# SCH_3_Heartrate_Motion_Sensors.net
KiCad netlist of a schematic drawn in Altium Designer
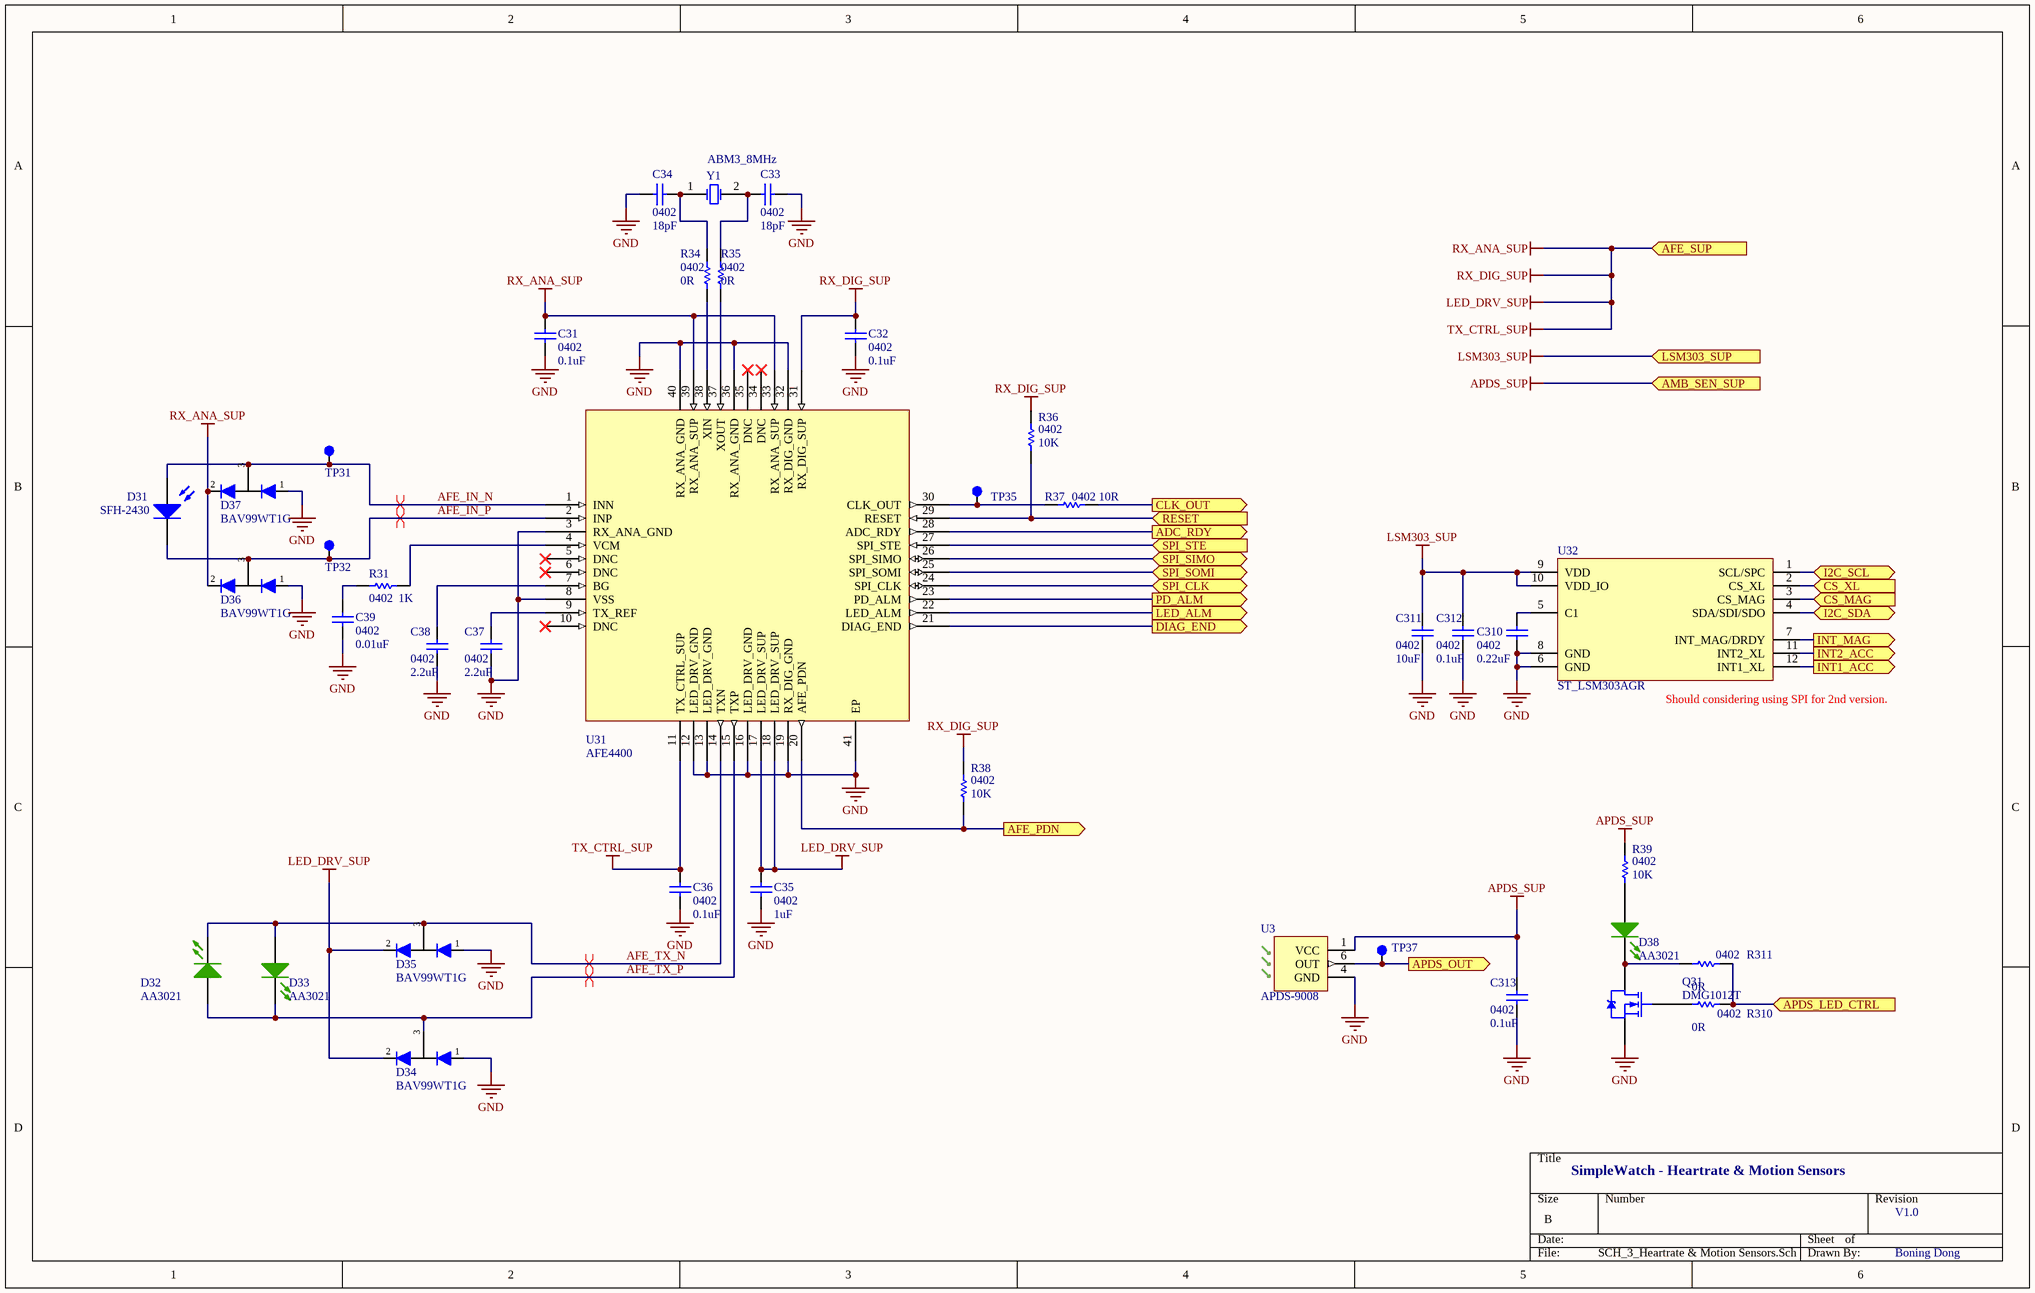
[diagram p0: SCH_3_Heartrate & Motion Sensors.SchDoc]

(export (version "E")
  (design (tool "Eeschema 10.0.6"))
  (components
    (comp (ref "C31")
      (value "0402")
      (footprint "CAPC1005X07N")
      (description "Capacitor")
      (fields (field (name "ALTIUM_VALUE") "0.1uF") (field (name "PUBLISHER") "Altium Limited"))
      (libsource (lib "Miscellaneous Devices") (part "Cap"))
    )
    (comp (ref "C32")
      (value "0402")
      (footprint "CAPC1005X07N")
      (description "Capacitor")
      (fields (field (name "ALTIUM_VALUE") "0.1uF") (field (name "PUBLISHER") "Altium Limited"))
      (libsource (lib "Miscellaneous Devices") (part "Cap"))
    )
    (comp (ref "C33")
      (value "0402")
      (footprint "CAPC1005X07N")
      (description "Capacitor")
      (fields (field (name "ALTIUM_VALUE") "18pF") (field (name "PUBLISHER") "Altium Limited"))
      (libsource (lib "Miscellaneous Devices") (part "Cap"))
    )
    (comp (ref "C34")
      (value "0402")
      (footprint "CAPC1005X07N")
      (description "Capacitor")
      (fields (field (name "ALTIUM_VALUE") "18pF") (field (name "PUBLISHER") "Altium Limited"))
      (libsource (lib "Miscellaneous Devices") (part "Cap"))
    )
    (comp (ref "C35")
      (value "0402")
      (footprint "CAPC1005X07N")
      (description "Capacitor")
      (fields (field (name "ALTIUM_VALUE") "1uF") (field (name "PUBLISHER") "Altium Limited"))
      (libsource (lib "Miscellaneous Devices") (part "Cap"))
    )
    (comp (ref "C36")
      (value "0402")
      (footprint "CAPC1005X07N")
      (description "Capacitor")
      (fields (field (name "ALTIUM_VALUE") "0.1uF") (field (name "PUBLISHER") "Altium Limited"))
      (libsource (lib "Miscellaneous Devices") (part "Cap"))
    )
    (comp (ref "C37")
      (value "0402")
      (footprint "CAPC1005X07N")
      (description "Capacitor")
      (fields (field (name "ALTIUM_VALUE") "2.2uF") (field (name "PUBLISHER") "Altium Limited"))
      (libsource (lib "Miscellaneous Devices") (part "Cap"))
    )
    (comp (ref "C38")
      (value "0402")
      (footprint "CAPC1005X07N")
      (description "Capacitor")
      (fields (field (name "ALTIUM_VALUE") "2.2uF") (field (name "PUBLISHER") "Altium Limited"))
      (libsource (lib "Miscellaneous Devices") (part "Cap"))
    )
    (comp (ref "C39")
      (value "0402")
      (footprint "CAPC1005X07N")
      (description "Capacitor")
      (fields (field (name "ALTIUM_VALUE") "0.01uF") (field (name "PUBLISHER") "Altium Limited"))
      (libsource (lib "Miscellaneous Devices") (part "Cap"))
    )
    (comp (ref "C310")
      (value "0402")
      (footprint "CAPC1005X07N")
      (description "Capacitor")
      (fields (field (name "ALTIUM_VALUE") "0.22uF") (field (name "PUBLISHER") "Altium Limited"))
      (libsource (lib "Miscellaneous Devices") (part "Cap"))
    )
    (comp (ref "C311")
      (value "0402")
      (footprint "CAPC1005X07N")
      (description "Capacitor")
      (fields (field (name "ALTIUM_VALUE") "10uF") (field (name "PUBLISHER") "Altium Limited"))
      (libsource (lib "Miscellaneous Devices") (part "Cap"))
    )
    (comp (ref "C312")
      (value "0402")
      (footprint "CAPC1005X07N")
      (description "Capacitor")
      (fields (field (name "ALTIUM_VALUE") "0.1uF") (field (name "PUBLISHER") "Altium Limited"))
      (libsource (lib "Miscellaneous Devices") (part "Cap"))
    )
    (comp (ref "C313")
      (value "0402")
      (footprint "CAPC1005X07N")
      (description "Capacitor")
      (fields (field (name "ALTIUM_VALUE") "0.1uF") (field (name "PUBLISHER") "Altium Limited"))
      (libsource (lib "Miscellaneous Devices") (part "Cap"))
    )
    (comp (ref "D31")
      (value "SFH-2430")
      (footprint "PHOTODIODE_OSRAM_SFH_2430")
      (description "Photosensitive Diode")
      (fields (field (name "PUBLISHER") "Altium Limited"))
      (libsource (lib "Miscellaneous Devices") (part "Photo Sen"))
    )
    (comp (ref "D32")
      (value "AA3021")
      (footprint "LED_KINGBRIGHT_AA3021")
      (description "General Green LED")
      (libsource (lib "Schematic_Diode") (part "LED_GREEN"))
    )
    (comp (ref "D33")
      (value "AA3021")
      (footprint "LED_KINGBRIGHT_AA3021")
      (description "General Green LED")
      (libsource (lib "Schematic_Diode") (part "LED_GREEN"))
    )
    (comp (ref "D34")
      (value "BAV99WT1G")
      (footprint "SOT65P200X125X90-3N")
      (description "DIODE ARRAY GP 100V 215MA SC70-3")
      (libsource (lib "Schematic_Diode") (part "BAV99WT1"))
    )
    (comp (ref "D35")
      (value "BAV99WT1G")
      (footprint "SOT65P200X125X90-3N")
      (description "DIODE ARRAY GP 100V 215MA SC70-3")
      (libsource (lib "Schematic_Diode") (part "BAV99WT1"))
    )
    (comp (ref "D36")
      (value "BAV99WT1G")
      (footprint "SOT65P200X125X90-3N")
      (description "DIODE ARRAY GP 100V 215MA SC70-3")
      (libsource (lib "Schematic_Diode") (part "BAV99WT1"))
    )
    (comp (ref "D37")
      (value "BAV99WT1G")
      (footprint "SOT65P200X125X90-3N")
      (description "DIODE ARRAY GP 100V 215MA SC70-3")
      (libsource (lib "Schematic_Diode") (part "BAV99WT1"))
    )
    (comp (ref "D38")
      (value "AA3021")
      (footprint "LED_KINGBRIGHT_AA3021")
      (description "General Green LED")
      (libsource (lib "Schematic_Diode") (part "LED_GREEN"))
    )
    (comp (ref "Q31")
      (value "DMG1012T")
      (footprint "SOT65P200X125X95-3N")
      (description "MOSFET N-CH 20V 630MA SOT-523")
      (fields (field (name "MANUFACTURER") "Diodes") (field (name "MANUFACTURER PART NUMBER") "DMG1012T-7"))
      (libsource (lib "Schematic_Transistors") (part "DMG1012T-7"))
    )
    (comp (ref "R31")
      (value "0402")
      (footprint "RESC1005X04N")
      (description "Resistor")
      (fields (field (name "ALTIUM_VALUE") "1K") (field (name "PUBLISHER") "Altium Limited"))
      (libsource (lib "Miscellaneous Devices") (part "Res1"))
    )
    (comp (ref "R34")
      (value "0402")
      (footprint "RESC1005X04N")
      (description "Resistor")
      (fields (field (name "ALTIUM_VALUE") "0R") (field (name "PUBLISHER") "Altium Limited"))
      (libsource (lib "Miscellaneous Devices") (part "Res1"))
    )
    (comp (ref "R35")
      (value "0402")
      (footprint "RESC1005X04N")
      (description "Resistor")
      (fields (field (name "ALTIUM_VALUE") "0R") (field (name "PUBLISHER") "Altium Limited"))
      (libsource (lib "Miscellaneous Devices") (part "Res1"))
    )
    (comp (ref "R36")
      (value "0402")
      (footprint "RESC1005X04N")
      (description "Resistor")
      (fields (field (name "ALTIUM_VALUE") "10K") (field (name "PUBLISHER") "Altium Limited"))
      (libsource (lib "Miscellaneous Devices") (part "Res1"))
    )
    (comp (ref "R37")
      (value "0402")
      (footprint "RESC1005X04N")
      (description "Resistor")
      (fields (field (name "ALTIUM_VALUE") "10R") (field (name "PUBLISHER") "Altium Limited"))
      (libsource (lib "Miscellaneous Devices") (part "Res1"))
    )
    (comp (ref "R38")
      (value "0402")
      (footprint "RESC1005X04N")
      (description "Resistor")
      (fields (field (name "ALTIUM_VALUE") "10K") (field (name "PUBLISHER") "Altium Limited"))
      (libsource (lib "Miscellaneous Devices") (part "Res1"))
    )
    (comp (ref "R39")
      (value "0402")
      (footprint "RESC1005X04N")
      (description "Resistor")
      (fields (field (name "ALTIUM_VALUE") "10K") (field (name "PUBLISHER") "Altium Limited"))
      (libsource (lib "Miscellaneous Devices") (part "Res1"))
    )
    (comp (ref "R310")
      (value "0402")
      (footprint "RESC1005X04N")
      (description "Resistor")
      (fields (field (name "ALTIUM_VALUE") "0R") (field (name "PUBLISHER") "Altium Limited"))
      (libsource (lib "Miscellaneous Devices") (part "Res1"))
    )
    (comp (ref "R311")
      (value "0402")
      (footprint "RESC1005X04N")
      (description "Resistor")
      (fields (field (name "ALTIUM_VALUE") "0R") (field (name "PUBLISHER") "Altium Limited"))
      (libsource (lib "Miscellaneous Devices") (part "Res1"))
    )
    (comp (ref "TP31")
      (value "TP")
      (footprint "TP100")
      (description "Test Point dot type")
      (libsource (lib "Schematic_Test_Points") (part "TP_A"))
    )
    (comp (ref "TP32")
      (value "TP")
      (footprint "TP100")
      (description "Test Point dot type")
      (libsource (lib "Schematic_Test_Points") (part "TP_A"))
    )
    (comp (ref "TP35")
      (value "TP")
      (footprint "TP100")
      (description "Test Point dot type")
      (libsource (lib "Schematic_Test_Points") (part "TP_A"))
    )
    (comp (ref "TP37")
      (value "TP")
      (footprint "TP100")
      (description "Test Point dot type")
      (libsource (lib "Schematic_Test_Points") (part "TP_A"))
    )
    (comp (ref "U3")
      (value "APDS-9008")
      (footprint "APDS-9008")
      (description "Optical Sensor Ambient 565nm Current 6-SMD, No Lead")
      (libsource (lib "Schematic_IC_Sensors") (part "APDS-9008"))
    )
    (comp (ref "U31")
      (value "AFE4400")
      (footprint "QFN50P600X600X100-40N_HS410")
      (description "Integrated Analog Front End (AFE) for Heart-Rate Monitors and Low-Cost Pulse Oximeters")
      (libsource (lib "Schematic_IC_Special") (part "AFE4400"))
    )
    (comp (ref "U32")
      (value "ST_LSM303AGR")
      (footprint "LGA12S50P4X4_200X200X100")
      (description "Accelerometer, Magnetometer, Temperature, 3 Axis Sensor I²C, SPI Output")
      (libsource (lib "Schematic_IC_Sensors") (part "ST_LSM303AGR"))
    )
    (comp (ref "Y1")
      (value "ABM3_8MHz")
      (footprint "ABRACON_ABM3")
      (description "Crystal Oscillator")
      (fields (field (name "PUBLISHER") "Altium Limited"))
      (libsource (lib "Miscellaneous Devices") (part "XTAL"))
    )
  )
  (nets
    (net (code "1") (name "/ADC_RDY") (class "Default")
      (node (ref "U31") (pin "28") (pinfunction "ADC_RDY_28") (pintype "output"))
    )
    (net (code "2") (name "/AFE_IN_N") (class "Default")
      (node (ref "D31") (pin "1") (pinfunction "A_1") (pintype "passive"))
      (node (ref "D37") (pin "3") (pinfunction "ANODE_3") (pintype "passive"))
      (node (ref "TP31") (pin "1") (pintype "passive"))
      (node (ref "U31") (pin "1") (pinfunction "INN_1") (pintype "input"))
    )
    (net (code "3") (name "/AFE_IN_P") (class "Default")
      (node (ref "D31") (pin "2") (pinfunction "K_2") (pintype "passive"))
      (node (ref "D36") (pin "3") (pinfunction "ANODE_3") (pintype "passive"))
      (node (ref "TP32") (pin "1") (pintype "passive"))
      (node (ref "U31") (pin "2") (pinfunction "INP_2") (pintype "input"))
    )
    (net (code "4") (name "/AFE_PDN") (class "Default")
      (node (ref "R38") (pin "1") (pinfunction "1_1") (pintype "passive"))
      (node (ref "U31") (pin "20") (pinfunction "AFE_PDN_20") (pintype "output"))
    )
    (net (code "5") (name "/AFE_TX_N") (class "Default")
      (node (ref "D32") (pin "2") (pinfunction "K_2") (pintype "passive"))
      (node (ref "D33") (pin "1") (pinfunction "A_1") (pintype "passive"))
      (node (ref "D35") (pin "3") (pinfunction "ANODE_3") (pintype "passive"))
      (node (ref "U31") (pin "14") (pinfunction "TXN_14") (pintype "output"))
    )
    (net (code "6") (name "/AFE_TX_P") (class "Default")
      (node (ref "D32") (pin "1") (pinfunction "A_1") (pintype "passive"))
      (node (ref "D33") (pin "2") (pinfunction "K_2") (pintype "passive"))
      (node (ref "D34") (pin "3") (pinfunction "ANODE_3") (pintype "passive"))
      (node (ref "U31") (pin "15") (pinfunction "TXP_15") (pintype "output"))
    )
    (net (code "7") (name "/APDS_LED_CTRL") (class "Default")
      (node (ref "R310") (pin "1") (pinfunction "1_1") (pintype "passive"))
      (node (ref "R311") (pin "1") (pinfunction "1_1") (pintype "passive"))
    )
    (net (code "8") (name "/APDS_OUT") (class "Default")
      (node (ref "TP37") (pin "1") (pintype "passive"))
      (node (ref "U3") (pin "6") (pinfunction "OUT_6") (pintype "output"))
    )
    (net (code "9") (name "/CLK_OUT") (class "Default")
      (node (ref "R37") (pin "1") (pinfunction "1_1") (pintype "passive"))
    )
    (net (code "10") (name "/CS_MAG") (class "Default")
      (node (ref "U32") (pin "3") (pinfunction "CS_MAG_3") (pintype "passive"))
    )
    (net (code "11") (name "/CS_XL") (class "Default")
      (node (ref "U32") (pin "2") (pinfunction "CS_XL_2") (pintype "passive"))
    )
    (net (code "12") (name "/DIAG_END") (class "Default")
      (node (ref "U31") (pin "21") (pinfunction "DIAG_END_21") (pintype "output"))
    )
    (net (code "13") (name "/I2C_SCL") (class "Default")
      (node (ref "U32") (pin "1") (pinfunction "SCL/SPC_1") (pintype "passive"))
    )
    (net (code "14") (name "/I2C_SDA") (class "Default")
      (node (ref "U32") (pin "4") (pinfunction "SDA/SDI/SDO_4") (pintype "passive"))
    )
    (net (code "15") (name "/INT1_ACC") (class "Default")
      (node (ref "U32") (pin "12") (pinfunction "INT1_XL_12") (pintype "passive"))
    )
    (net (code "16") (name "/INT2_ACC") (class "Default")
      (node (ref "U32") (pin "11") (pinfunction "INT2_XL_11") (pintype "passive"))
    )
    (net (code "17") (name "/INT_MAG") (class "Default")
      (node (ref "U32") (pin "7") (pinfunction "INT_MAG/DRDY_7") (pintype "passive"))
    )
    (net (code "18") (name "/LED_ALM") (class "Default")
      (node (ref "U31") (pin "22") (pinfunction "LED_ALM_22") (pintype "output"))
    )
    (net (code "19") (name "/PD_ALM") (class "Default")
      (node (ref "U31") (pin "23") (pinfunction "PD_ALM_23") (pintype "output"))
    )
    (net (code "20") (name "/RESET") (class "Default")
      (node (ref "R36") (pin "1") (pinfunction "1_1") (pintype "passive"))
      (node (ref "U31") (pin "29") (pinfunction "RESET_29") (pintype "input"))
    )
    (net (code "21") (name "/SPI_CLK") (class "Default")
      (node (ref "U31") (pin "24") (pinfunction "SPI_CLK_24") (pintype "bidirectional"))
    )
    (net (code "22") (name "/SPI_SIMO") (class "Default")
      (node (ref "U31") (pin "26") (pinfunction "SPI_SIMO_26") (pintype "bidirectional"))
    )
    (net (code "23") (name "/SPI_SOMI") (class "Default")
      (node (ref "U31") (pin "25") (pinfunction "SPI_SOMI_25") (pintype "bidirectional"))
    )
    (net (code "24") (name "/SPI_STE") (class "Default")
      (node (ref "U31") (pin "27") (pinfunction "SPI_STE_27") (pintype "input"))
    )
    (net (code "25") (name "APDS_SUP") (class "Default")
      (node (ref "C313") (pin "2") (pinfunction "2_2") (pintype "passive"))
      (node (ref "R39") (pin "2") (pinfunction "2_2") (pintype "passive"))
      (node (ref "U3") (pin "1") (pinfunction "VCC_1") (pintype "passive"))
    )
    (net (code "26") (name "GND") (class "Default")
      (node (ref "C31") (pin "1") (pinfunction "1_1") (pintype "passive"))
      (node (ref "C310") (pin "1") (pinfunction "1_1") (pintype "passive"))
      (node (ref "C311") (pin "1") (pinfunction "1_1") (pintype "passive"))
      (node (ref "C312") (pin "1") (pinfunction "1_1") (pintype "passive"))
      (node (ref "C313") (pin "1") (pinfunction "1_1") (pintype "passive"))
      (node (ref "C32") (pin "1") (pinfunction "1_1") (pintype "passive"))
      (node (ref "C33") (pin "1") (pinfunction "1_1") (pintype "passive"))
      (node (ref "C34") (pin "2") (pinfunction "2_2") (pintype "passive"))
      (node (ref "C35") (pin "1") (pinfunction "1_1") (pintype "passive"))
      (node (ref "C36") (pin "1") (pinfunction "1_1") (pintype "passive"))
      (node (ref "C37") (pin "1") (pinfunction "1_1") (pintype "passive"))
      (node (ref "C38") (pin "1") (pinfunction "1_1") (pintype "passive"))
      (node (ref "C39") (pin "1") (pinfunction "1_1") (pintype "passive"))
      (node (ref "D34") (pin "1") (pinfunction "ANODE_1") (pintype "passive"))
      (node (ref "D35") (pin "1") (pinfunction "ANODE_1") (pintype "passive"))
      (node (ref "D36") (pin "1") (pinfunction "ANODE_1") (pintype "passive"))
      (node (ref "D37") (pin "1") (pinfunction "ANODE_1") (pintype "passive"))
      (node (ref "Q31") (pin "2") (pinfunction "S_2") (pintype "passive"))
      (node (ref "U3") (pin "4") (pinfunction "GND_4") (pintype "passive"))
      (node (ref "U31") (pin "12") (pinfunction "LED_DRV_GND_12") (pintype "passive"))
      (node (ref "U31") (pin "13") (pinfunction "LED_DRV_GND_13") (pintype "passive"))
      (node (ref "U31") (pin "16") (pinfunction "LED_DRV_GND_16") (pintype "passive"))
      (node (ref "U31") (pin "19") (pinfunction "RX_DIG_GND_19") (pintype "passive"))
      (node (ref "U31") (pin "3") (pinfunction "RX_ANA_GND_3") (pintype "passive"))
      (node (ref "U31") (pin "32") (pinfunction "RX_DIG_GND_32") (pintype "passive"))
      (node (ref "U31") (pin "36") (pinfunction "RX_ANA_GND_36") (pintype "passive"))
      (node (ref "U31") (pin "40") (pinfunction "RX_ANA_GND_40") (pintype "passive"))
      (node (ref "U31") (pin "41") (pinfunction "EP_41") (pintype "passive"))
      (node (ref "U31") (pin "8") (pinfunction "VSS_8") (pintype "passive"))
      (node (ref "U32") (pin "6") (pinfunction "GND_6") (pintype "passive"))
      (node (ref "U32") (pin "8") (pinfunction "GND_8") (pintype "passive"))
    )
    (net (code "27") (name "LED_DRV_SUP") (class "Default")
      (node (ref "C31") (pin "2") (pinfunction "2_2") (pintype "passive"))
      (node (ref "C32") (pin "2") (pinfunction "2_2") (pintype "passive"))
      (node (ref "C35") (pin "2") (pinfunction "2_2") (pintype "passive"))
      (node (ref "C36") (pin "2") (pinfunction "2_2") (pintype "passive"))
      (node (ref "D34") (pin "2") (pinfunction "ANODE_2") (pintype "passive"))
      (node (ref "D35") (pin "2") (pinfunction "ANODE_2") (pintype "passive"))
      (node (ref "D36") (pin "2") (pinfunction "ANODE_2") (pintype "passive"))
      (node (ref "D37") (pin "2") (pinfunction "ANODE_2") (pintype "passive"))
      (node (ref "R36") (pin "2") (pinfunction "2_2") (pintype "passive"))
      (node (ref "R38") (pin "2") (pinfunction "2_2") (pintype "passive"))
      (node (ref "U31") (pin "11") (pinfunction "TX_CTRL_SUP_11") (pintype "passive"))
      (node (ref "U31") (pin "17") (pinfunction "LED_DRV_SUP_17") (pintype "passive"))
      (node (ref "U31") (pin "18") (pinfunction "LED_DRV_SUP_18") (pintype "passive"))
      (node (ref "U31") (pin "31") (pinfunction "RX_DIG_SUP_31") (pintype "input"))
      (node (ref "U31") (pin "33") (pinfunction "RX_ANA_SUP_33") (pintype "input"))
      (node (ref "U31") (pin "39") (pinfunction "RX_ANA_SUP_39") (pintype "input"))
    )
    (net (code "28") (name "LSM303_SUP") (class "Default")
      (node (ref "C311") (pin "2") (pinfunction "2_2") (pintype "passive"))
      (node (ref "C312") (pin "2") (pinfunction "2_2") (pintype "passive"))
      (node (ref "U32") (pin "10") (pinfunction "VDD_IO_10") (pintype "passive"))
      (node (ref "U32") (pin "9") (pinfunction "VDD_9") (pintype "passive"))
    )
    (net (code "29") (name "Net-(C39-Pad2)") (class "Default")
      (node (ref "C39") (pin "2") (pinfunction "2_2") (pintype "passive"))
      (node (ref "R31") (pin "1") (pinfunction "1_1") (pintype "passive"))
    )
    (net (code "30") (name "Net-(D38-A)") (class "Default")
      (node (ref "D38") (pin "1") (pinfunction "A_1") (pintype "passive"))
      (node (ref "R39") (pin "1") (pinfunction "1_1") (pintype "passive"))
    )
    (net (code "31") (name "Net-(D38-K)") (class "Default")
      (node (ref "D38") (pin "2") (pinfunction "K_2") (pintype "passive"))
      (node (ref "Q31") (pin "3") (pinfunction "D_3") (pintype "passive"))
      (node (ref "R311") (pin "2") (pinfunction "2_2") (pintype "passive"))
    )
    (net (code "32") (name "Net-(Q31-G)") (class "Default")
      (node (ref "Q31") (pin "1") (pinfunction "G_1") (pintype "passive"))
      (node (ref "R310") (pin "2") (pinfunction "2_2") (pintype "passive"))
    )
    (net (code "33") (name "Net-(U31-BG)") (class "Default")
      (node (ref "C38") (pin "2") (pinfunction "2_2") (pintype "passive"))
      (node (ref "U31") (pin "7") (pinfunction "BG_7") (pintype "input"))
    )
    (net (code "34") (name "Net-(U31-CLK_OUT)") (class "Default")
      (node (ref "R37") (pin "2") (pinfunction "2_2") (pintype "passive"))
      (node (ref "TP35") (pin "1") (pintype "passive"))
      (node (ref "U31") (pin "30") (pinfunction "CLK_OUT_30") (pintype "output"))
    )
    (net (code "35") (name "Net-(U31-TX_REF)") (class "Default")
      (node (ref "C37") (pin "2") (pinfunction "2_2") (pintype "passive"))
      (node (ref "U31") (pin "9") (pinfunction "TX_REF_9") (pintype "input"))
    )
    (net (code "36") (name "Net-(U31-VCM)") (class "Default")
      (node (ref "R31") (pin "2") (pinfunction "2_2") (pintype "passive"))
      (node (ref "U31") (pin "4") (pinfunction "VCM_4") (pintype "input"))
    )
    (net (code "37") (name "Net-(U31-XIN)") (class "Default")
      (node (ref "R34") (pin "1") (pinfunction "1_1") (pintype "passive"))
      (node (ref "U31") (pin "38") (pinfunction "XIN_38") (pintype "input"))
    )
    (net (code "38") (name "Net-(U31-XOUT)") (class "Default")
      (node (ref "R35") (pin "1") (pinfunction "1_1") (pintype "passive"))
      (node (ref "U31") (pin "37") (pinfunction "XOUT_37") (pintype "input"))
    )
    (net (code "39") (name "Net-(U32-C1)") (class "Default")
      (node (ref "C310") (pin "2") (pinfunction "2_2") (pintype "passive"))
      (node (ref "U32") (pin "5") (pinfunction "C1_5") (pintype "passive"))
    )
    (net (code "40") (name "Net-(Y1-OSC1)") (class "Default")
      (node (ref "C34") (pin "1") (pinfunction "1_1") (pintype "passive"))
      (node (ref "R34") (pin "2") (pinfunction "2_2") (pintype "passive"))
      (node (ref "Y1") (pin "1") (pinfunction "OSC1_1") (pintype "passive"))
    )
    (net (code "41") (name "Net-(Y1-OSC2)") (class "Default")
      (node (ref "C33") (pin "2") (pinfunction "2_2") (pintype "passive"))
      (node (ref "R35") (pin "2") (pinfunction "2_2") (pintype "passive"))
      (node (ref "Y1") (pin "2") (pinfunction "OSC2_2") (pintype "passive"))
    )
    (net (code "42") (name "unconnected-(U31-DNC-Pad5)") (class "Default")
      (node (ref "U31") (pin "5") (pinfunction "DNC_5") (pintype "input+no_connect"))
    )
    (net (code "43") (name "unconnected-(U31-DNC-Pad6)") (class "Default")
      (node (ref "U31") (pin "6") (pinfunction "DNC_6") (pintype "input+no_connect"))
    )
    (net (code "44") (name "unconnected-(U31-DNC-Pad10)") (class "Default")
      (node (ref "U31") (pin "10") (pinfunction "DNC_10") (pintype "input+no_connect"))
    )
    (net (code "45") (name "unconnected-(U31-DNC-Pad34)") (class "Default")
      (node (ref "U31") (pin "34") (pinfunction "DNC_34") (pintype "passive+no_connect"))
    )
    (net (code "46") (name "unconnected-(U31-DNC-Pad35)") (class "Default")
      (node (ref "U31") (pin "35") (pinfunction "DNC_35") (pintype "passive+no_connect"))
    )
  )
)
